# SCHE_Doan2.net
KiCad netlist of a schematic drawn in Altium Designer
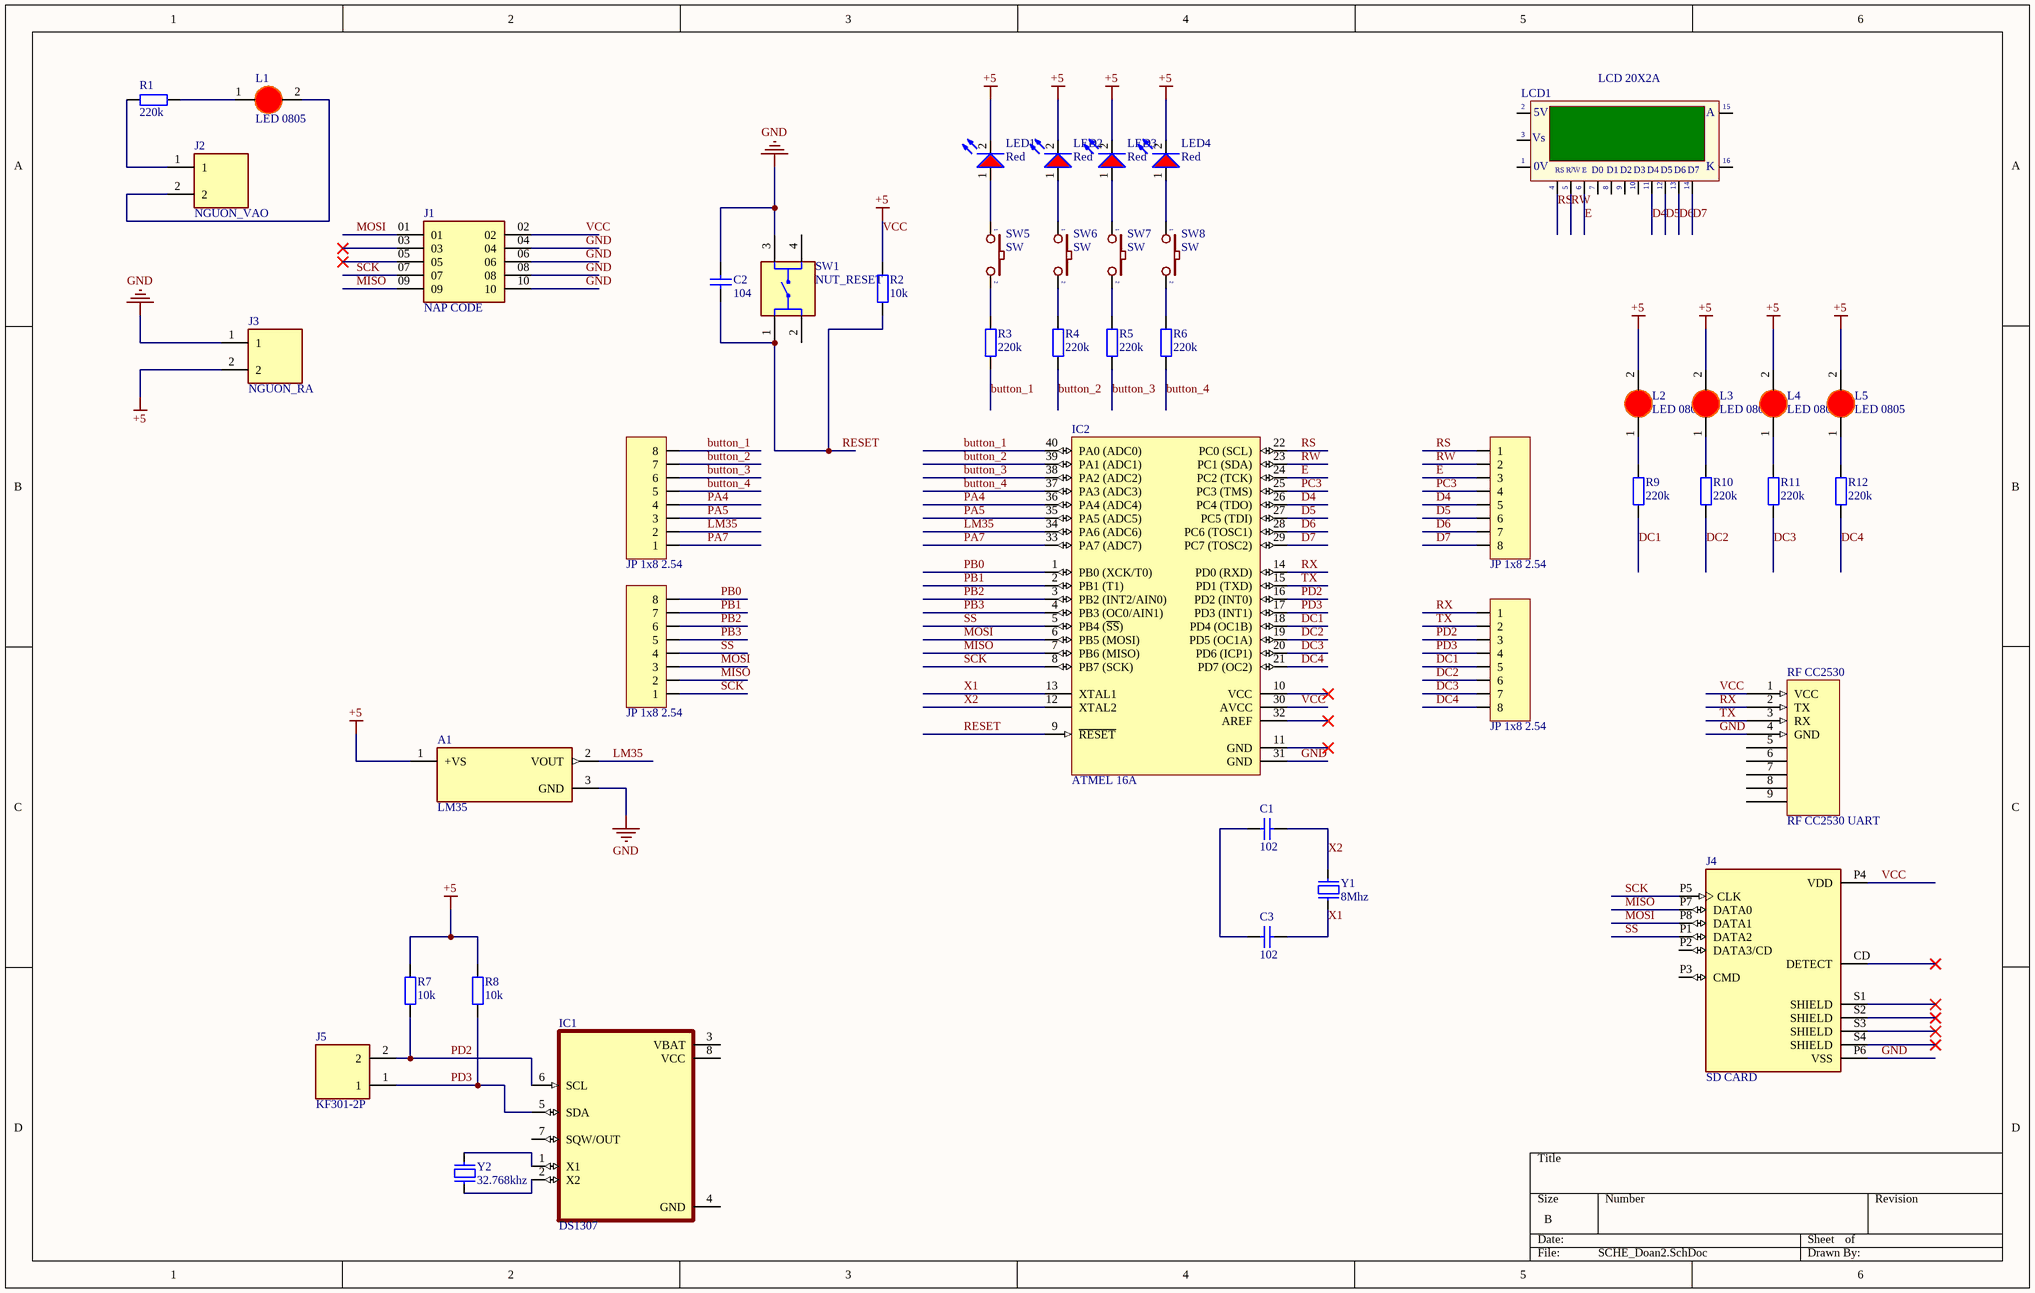
[diagram p0: SCHE_Doan2.SchDoc]

(export (version "E")
  (design (tool "Eeschema 10.0.6"))
  (components
    (comp (ref "A1")
      (value "LM35")
      (footprint "TO92127P521H735-3")
      (fields (field (name "MP") "LM35DZ/NOPB"))
      (libsource (lib "LM35DZ_NOPB") (part "LM35DZ/NOPB"))
    )
    (comp (ref "C1")
      (value "102")
      (footprint "tu gom")
      (description "Cắm")
      (libsource (lib "Altium_Lib_by_KhueNguyenCreator") (part "Tu gom 102 50V"))
    )
    (comp (ref "C2")
      (value "104")
      (footprint "tu gom")
      (description "Cắm")
      (libsource (lib "Altium_Lib_by_KhueNguyenCreator") (part "Tu gom 104 50V"))
    )
    (comp (ref "C3")
      (value "102")
      (footprint "tu gom")
      (description "Cắm")
      (libsource (lib "Altium_Lib_by_KhueNguyenCreator") (part "Tu gom 102 50V"))
    )
    (comp (ref "IC1")
      (value "DS1307")
      (footprint "DIP794W47P254L991H457Q8")
      (description "Real Time Clock _RTC_ IC Clock/Calendar 56B IÂ²C, 2-Wire Serial 8-DIP _0.300, 7.62mm_")
      (fields (field (name "MF") "Maxim Integrated"))
      (libsource (lib "DS1307") (part "DS1307"))
    )
    (comp (ref "IC2")
      (value "ATMEL 16A")
      (footprint "DIP40/W0.6")
      (description "8-Bit AVR Microcontroller with 16K Bytes of In-System Programmable Flash Memory")
      (libsource (lib "TechMT.VN_Lib_Project v2") (part "ATmega16A-PU"))
    )
    (comp (ref "J1")
      (value "NAP CODE")
      (footprint "SAMTEC_ZSS-105-09-L-D-1290")
      (fields (field (name "MP") "ZSS-105-09-L-D-1290"))
      (libsource (lib "ZSS-105-09-L-D-1290") (part "ZSS-105-09-L-D-1290"))
    )
    (comp (ref "J2")
      (value "NGUON_VAO")
      (footprint "HANDSON_KF301-2P")
      (description "2 Pin Terminal Block 5mm Pitch")
      (fields (field (name "MF") "Handson Technology") (field (name "MP") "KF301-2P"))
      (libsource (lib "") (part "KF301-2P_1"))
    )
    (comp (ref "J3")
      (value "NGUON_RA")
      (footprint "HANDSON_KF301-2P")
      (description "2 Pin Terminal Block 5mm Pitch")
      (fields (field (name "MF") "Handson Technology") (field (name "MP") "KF301-2P"))
      (libsource (lib "") (part "KF301-2P_1"))
    )
    (comp (ref "J4")
      (value "SD CARD")
      (footprint "GCT_MEM2051-00-195-00-A_REVD1")
      (fields (field (name "MP") "MEM2051-00-195-00-A_REVD1"))
      (libsource (lib "MEM2051-00-195-00-A_REVD1") (part "MEM2051-00-195-00-A_REVD1"))
    )
    (comp (ref "J5")
      (value "KF301-2P")
      (footprint "HANDSON_KF301-2P")
      (description "2 Pin Terminal Block 5mm Pitch")
      (fields (field (name "MF") "Handson Technology"))
      (libsource (lib "KF301-2P") (part "KF301-2P"))
    )
    (comp (ref "JP1")
      (value "JP 1x8 2.54")
      (footprint "JP 1x8 CT")
      (description "Cắm")
      (libsource (lib "") (part "JP 1x8 2.54 Cai Thang_1"))
    )
    (comp (ref "JP2")
      (value "JP 1x8 2.54")
      (footprint "JP 1x8 CT")
      (description "Cắm")
      (libsource (lib "Altium_Lib_by_KhueNguyenCreator") (part "JP 1x8 2.54 Cai Thang"))
    )
    (comp (ref "JP3")
      (value "JP 1x8 2.54")
      (footprint "JP 1x8 CT")
      (description "Cắm")
      (libsource (lib "Altium_Lib_by_KhueNguyenCreator") (part "JP 1x8 2.54 Cai Thang"))
    )
    (comp (ref "JP4")
      (value "JP 1x8 2.54")
      (footprint "JP 1x8 CT")
      (description "Cắm")
      (libsource (lib "") (part "JP 1x8 2.54 Cai Thang_1"))
    )
    (comp (ref "L1")
      (value "LED 0805")
      (footprint "LED-0805-Red")
      (description "Dán")
      (libsource (lib "Altium_Lib_by_KhueNguyenCreator") (part "LED 0805 Do"))
    )
    (comp (ref "L2")
      (value "LED 0805")
      (footprint "LED-0805-Red")
      (description "Dán")
      (libsource (lib "Altium_Lib_by_KhueNguyenCreator") (part "LED 0805 Do"))
    )
    (comp (ref "L3")
      (value "LED 0805")
      (footprint "LED-0805-Red")
      (description "Dán")
      (libsource (lib "Altium_Lib_by_KhueNguyenCreator") (part "LED 0805 Do"))
    )
    (comp (ref "L4")
      (value "LED 0805")
      (footprint "LED-0805-Red")
      (description "Dán")
      (libsource (lib "Altium_Lib_by_KhueNguyenCreator") (part "LED 0805 Do"))
    )
    (comp (ref "L5")
      (value "LED 0805")
      (footprint "LED-0805-Red")
      (description "Dán")
      (libsource (lib "Altium_Lib_by_KhueNguyenCreator") (part "LED 0805 Do"))
    )
    (comp (ref "LCD1")
      (value "LCD 20X2A")
      (footprint "LCD16X2")
      (description "LCD dipslay 16 char, 2 line")
      (libsource (lib "TechMT.VN_Lib_Project v1.0") (part "LCD16x2A"))
    )
    (comp (ref "LED1")
      (value "Red")
      (footprint "LED-RED-0805")
      (description "LED Red 2mA 1.8V 0805")
      (fields (field (name "Comment") "LED-Red"))
      (libsource (lib "TechMT.VN_Lib_Project v2") (part "Led-Red"))
    )
    (comp (ref "LED2")
      (value "Red")
      (footprint "LED-RED-0805")
      (description "LED Red 2mA 1.8V 0805")
      (fields (field (name "Comment") "LED-Red"))
      (libsource (lib "TechMT.VN_Lib_Project v2") (part "Led-Red"))
    )
    (comp (ref "LED3")
      (value "Red")
      (footprint "LED-RED-0805")
      (description "LED Red 2mA 1.8V 0805")
      (fields (field (name "Comment") "LED-Red"))
      (libsource (lib "TechMT.VN_Lib_Project v2") (part "Led-Red"))
    )
    (comp (ref "LED4")
      (value "Red")
      (footprint "LED-RED-0805")
      (description "LED Red 2mA 1.8V 0805")
      (fields (field (name "Comment") "LED-Red"))
      (libsource (lib "TechMT.VN_Lib_Project v2") (part "Led-Red"))
    )
    (comp (ref "R1")
      (value "220k")
      (footprint "tro smd 0805")
      (description "Dán")
      (libsource (lib "Altium_Lib_by_KhueNguyenCreator") (part "Tro 0805 1% 220k"))
    )
    (comp (ref "R2")
      (value "10k")
      (footprint "tro smd 0805")
      (description "Dán")
      (libsource (lib "Altium_Lib_by_KhueNguyenCreator") (part "Tro 0805 1% 10k"))
    )
    (comp (ref "R3")
      (value "220k")
      (footprint "tro smd 0805")
      (description "Dán")
      (libsource (lib "Altium_Lib_by_KhueNguyenCreator") (part "Tro 0805 1% 220k"))
    )
    (comp (ref "R4")
      (value "220k")
      (footprint "tro smd 0805")
      (description "Dán")
      (libsource (lib "Altium_Lib_by_KhueNguyenCreator") (part "Tro 0805 1% 220k"))
    )
    (comp (ref "R5")
      (value "220k")
      (footprint "tro smd 0805")
      (description "Dán")
      (libsource (lib "Altium_Lib_by_KhueNguyenCreator") (part "Tro 0805 1% 220k"))
    )
    (comp (ref "R6")
      (value "220k")
      (footprint "tro smd 0805")
      (description "Dán")
      (libsource (lib "Altium_Lib_by_KhueNguyenCreator") (part "Tro 0805 1% 220k"))
    )
    (comp (ref "R7")
      (value "10k")
      (footprint "tro smd 0805")
      (description "Dán")
      (libsource (lib "Altium_Lib_by_KhueNguyenCreator") (part "Tro 0805 1% 10k"))
    )
    (comp (ref "R8")
      (value "10k")
      (footprint "tro smd 0805")
      (description "Dán")
      (libsource (lib "Altium_Lib_by_KhueNguyenCreator") (part "Tro 0805 1% 10k"))
    )
    (comp (ref "R9")
      (value "220k")
      (footprint "tro smd 0805")
      (description "Dán")
      (libsource (lib "Altium_Lib_by_KhueNguyenCreator") (part "Tro 0805 1% 220k"))
    )
    (comp (ref "R10")
      (value "220k")
      (footprint "tro smd 0805")
      (description "Dán")
      (libsource (lib "Altium_Lib_by_KhueNguyenCreator") (part "Tro 0805 1% 220k"))
    )
    (comp (ref "R11")
      (value "220k")
      (footprint "tro smd 0805")
      (description "Dán")
      (libsource (lib "Altium_Lib_by_KhueNguyenCreator") (part "Tro 0805 1% 220k"))
    )
    (comp (ref "R12")
      (value "220k")
      (footprint "tro smd 0805")
      (description "Dán")
      (libsource (lib "Altium_Lib_by_KhueNguyenCreator") (part "Tro 0805 1% 220k"))
    )
    (comp (ref "RF CC2530")
      (value "RF CC2530 UART")
      (footprint "CC2530")
      (description "IC chính: CC2530, 15.5 x 31.5mm")
      (libsource (lib "TechMT.VN_Lib_Project v2") (part "RF CC2530 UART 2.4G"))
    )
    (comp (ref "SW1")
      (value "NUT_RESET")
      (footprint "SW_1825910-6-4")
      (description "Switch Tactile OFF (ON) SPST Round Button PC Pins 0.05A 24VDC 100000Cycles 1.57N Thru-Hole Loose")
      (fields (field (name "MP") "1825910-6"))
      (libsource (lib "1825910-6") (part "1825910-6"))
    )
    (comp (ref "SW5")
      (value "SW")
      (footprint "SW1-SMD")
      (description "Switch button 2 pin")
      (libsource (lib "TechMT.VN_Lib_Project v2") (part "SW2"))
    )
    (comp (ref "SW6")
      (value "SW")
      (footprint "SW1-SMD")
      (description "Switch button 2 pin")
      (libsource (lib "TechMT.VN_Lib_Project v2") (part "SW2"))
    )
    (comp (ref "SW7")
      (value "SW")
      (footprint "SW1-SMD")
      (description "Switch button 2 pin")
      (libsource (lib "TechMT.VN_Lib_Project v2") (part "SW2"))
    )
    (comp (ref "SW8")
      (value "SW")
      (footprint "SW1-SMD")
      (description "Switch button 2 pin")
      (libsource (lib "TechMT.VN_Lib_Project v2") (part "SW2"))
    )
    (comp (ref "Y1")
      (value "8Mhz")
      (footprint "Thach Anh 2 Chan 32,768 KHz")
      (description "Crystal For all Crystal 2pin.")
      (libsource (lib "Altium_Lib_by_KhueNguyenCreator") (part "Thach Anh 2 chan 32,768 Khz"))
    )
    (comp (ref "Y2")
      (value "32.768khz")
      (footprint "Thach Anh 2 Chan 32,768 KHz")
      (description "Crystal For all Crystal 2pin.")
      (libsource (lib "Altium_Lib_by_KhueNguyenCreator") (part "Thach Anh 2 chan 32,768 Khz"))
    )
  )
  (nets
    (net (code "1") (name "+5") (class "Default")
      (node (ref "A1") (pin "1") (pinfunction "+VS_1") (pintype "power_in"))
      (node (ref "IC2") (pin "30") (pinfunction "AVCC_30") (pintype "power_in"))
      (node (ref "J1") (pin "02") (pinfunction "02_02") (pintype "passive"))
      (node (ref "J3") (pin "2") (pinfunction "2_2") (pintype "passive"))
      (node (ref "J4") (pin "P4") (pinfunction "VDD_P4") (pintype "power_in"))
      (node (ref "L2") (pin "2") (pinfunction "K_2") (pintype "passive"))
      (node (ref "L3") (pin "2") (pinfunction "K_2") (pintype "passive"))
      (node (ref "L4") (pin "2") (pinfunction "K_2") (pintype "passive"))
      (node (ref "L5") (pin "2") (pinfunction "K_2") (pintype "passive"))
      (node (ref "LED1") (pin "2") (pinfunction "K_2") (pintype "passive"))
      (node (ref "LED2") (pin "2") (pinfunction "K_2") (pintype "passive"))
      (node (ref "LED3") (pin "2") (pinfunction "K_2") (pintype "passive"))
      (node (ref "LED4") (pin "2") (pinfunction "K_2") (pintype "passive"))
      (node (ref "R2") (pin "2") (pinfunction "2_2") (pintype "passive"))
      (node (ref "R7") (pin "2") (pinfunction "2_2") (pintype "passive"))
      (node (ref "R8") (pin "2") (pinfunction "2_2") (pintype "passive"))
      (node (ref "RF CC2530") (pin "1") (pinfunction "VCC_1") (pintype "input"))
    )
    (net (code "2") (name "/D4") (class "Default")
      (node (ref "IC2") (pin "26") (pinfunction "PC4_(TDO)_26") (pintype "bidirectional"))
      (node (ref "JP1") (pin "5") (pinfunction "5_5") (pintype "passive"))
      (node (ref "LCD1") (pin "11") (pinfunction "D4_11") (pintype "passive"))
    )
    (net (code "3") (name "/D5") (class "Default")
      (node (ref "IC2") (pin "27") (pinfunction "PC5_(TDI)_27") (pintype "bidirectional"))
      (node (ref "JP1") (pin "6") (pinfunction "6_6") (pintype "passive"))
      (node (ref "LCD1") (pin "12") (pinfunction "D5_12") (pintype "passive"))
    )
    (net (code "4") (name "/D6") (class "Default")
      (node (ref "IC2") (pin "28") (pinfunction "PC6_(TOSC1)_28") (pintype "bidirectional"))
      (node (ref "JP1") (pin "7") (pinfunction "7_7") (pintype "passive"))
      (node (ref "LCD1") (pin "13") (pinfunction "D6_13") (pintype "passive"))
    )
    (net (code "5") (name "/D7") (class "Default")
      (node (ref "IC2") (pin "29") (pinfunction "PC7_(TOSC2)_29") (pintype "bidirectional"))
      (node (ref "JP1") (pin "8") (pinfunction "8_8") (pintype "passive"))
      (node (ref "LCD1") (pin "14") (pinfunction "D7_14") (pintype "passive"))
    )
    (net (code "6") (name "/DC1") (class "Default")
      (node (ref "IC2") (pin "18") (pinfunction "PD4_(OC1B)_18") (pintype "bidirectional"))
      (node (ref "JP4") (pin "5") (pinfunction "5_5") (pintype "passive"))
      (node (ref "R9") (pin "1") (pinfunction "1_1") (pintype "passive"))
    )
    (net (code "7") (name "/DC2") (class "Default")
      (node (ref "IC2") (pin "19") (pinfunction "PD5_(OC1A)_19") (pintype "bidirectional"))
      (node (ref "JP4") (pin "6") (pinfunction "6_6") (pintype "passive"))
      (node (ref "R10") (pin "1") (pinfunction "1_1") (pintype "passive"))
    )
    (net (code "8") (name "/DC3") (class "Default")
      (node (ref "IC2") (pin "20") (pinfunction "PD6_(ICP1)_20") (pintype "bidirectional"))
      (node (ref "JP4") (pin "7") (pinfunction "7_7") (pintype "passive"))
      (node (ref "R11") (pin "1") (pinfunction "1_1") (pintype "passive"))
    )
    (net (code "9") (name "/DC4") (class "Default")
      (node (ref "IC2") (pin "21") (pinfunction "PD7_(OC2)_21") (pintype "bidirectional"))
      (node (ref "JP4") (pin "8") (pinfunction "8_8") (pintype "passive"))
      (node (ref "R12") (pin "1") (pinfunction "1_1") (pintype "passive"))
    )
    (net (code "10") (name "/E") (class "Default")
      (node (ref "IC2") (pin "24") (pinfunction "PC2_(TCK)_24") (pintype "bidirectional"))
      (node (ref "JP1") (pin "3") (pinfunction "3_3") (pintype "passive"))
      (node (ref "LCD1") (pin "6") (pinfunction "~{EN}_6") (pintype "passive"))
    )
    (net (code "11") (name "/LM35") (class "Default")
      (node (ref "A1") (pin "2") (pinfunction "VOUT_2") (pintype "output"))
      (node (ref "IC2") (pin "34") (pinfunction "PA6_(ADC6)_34") (pintype "bidirectional"))
      (node (ref "JP2") (pin "2") (pinfunction "2_2") (pintype "passive"))
    )
    (net (code "12") (name "/MISO") (class "Default")
      (node (ref "IC2") (pin "7") (pinfunction "PB6_(MISO)_7") (pintype "bidirectional"))
      (node (ref "J1") (pin "09") (pinfunction "09_09") (pintype "passive"))
      (node (ref "J4") (pin "P7") (pinfunction "DATA0_P7") (pintype "bidirectional"))
      (node (ref "JP3") (pin "2") (pinfunction "2_2") (pintype "passive"))
    )
    (net (code "13") (name "/MOSI") (class "Default")
      (node (ref "IC2") (pin "6") (pinfunction "PB5_(MOSI)_6") (pintype "bidirectional"))
      (node (ref "J1") (pin "01") (pinfunction "01_01") (pintype "passive"))
      (node (ref "J4") (pin "P8") (pinfunction "DATA1_P8") (pintype "bidirectional"))
      (node (ref "JP3") (pin "3") (pinfunction "3_3") (pintype "passive"))
    )
    (net (code "14") (name "/PA4") (class "Default")
      (node (ref "IC2") (pin "36") (pinfunction "PA4_(ADC4)_36") (pintype "bidirectional"))
      (node (ref "JP2") (pin "4") (pinfunction "4_4") (pintype "passive"))
    )
    (net (code "15") (name "/PA5") (class "Default")
      (node (ref "IC2") (pin "35") (pinfunction "PA5_(ADC5)_35") (pintype "bidirectional"))
      (node (ref "JP2") (pin "3") (pinfunction "3_3") (pintype "passive"))
    )
    (net (code "16") (name "/PA7") (class "Default")
      (node (ref "IC2") (pin "33") (pinfunction "PA7_(ADC7)_33") (pintype "bidirectional"))
      (node (ref "JP2") (pin "1") (pinfunction "1_1") (pintype "passive"))
    )
    (net (code "17") (name "/PB0") (class "Default")
      (node (ref "IC2") (pin "1") (pinfunction "PB0_(XCK/T0)_1") (pintype "bidirectional"))
      (node (ref "JP3") (pin "8") (pinfunction "8_8") (pintype "passive"))
    )
    (net (code "18") (name "/PB1") (class "Default")
      (node (ref "IC2") (pin "2") (pinfunction "PB1_(T1)_2") (pintype "bidirectional"))
      (node (ref "JP3") (pin "7") (pinfunction "7_7") (pintype "passive"))
    )
    (net (code "19") (name "/PB2") (class "Default")
      (node (ref "IC2") (pin "3") (pinfunction "PB2_(INT2/AIN0)_3") (pintype "bidirectional"))
      (node (ref "JP3") (pin "6") (pinfunction "6_6") (pintype "passive"))
    )
    (net (code "20") (name "/PB3") (class "Default")
      (node (ref "IC2") (pin "4") (pinfunction "PB3_(OC0/AIN1)_4") (pintype "bidirectional"))
      (node (ref "JP3") (pin "5") (pinfunction "5_5") (pintype "passive"))
    )
    (net (code "21") (name "/PC3") (class "Default")
      (node (ref "IC2") (pin "25") (pinfunction "PC3_(TMS)_25") (pintype "bidirectional"))
      (node (ref "JP1") (pin "4") (pinfunction "4_4") (pintype "passive"))
    )
    (net (code "22") (name "/PD2") (class "Default")
      (node (ref "IC1") (pin "6") (pinfunction "SCL_6") (pintype "input"))
      (node (ref "IC2") (pin "16") (pinfunction "PD2_(INT0)_16") (pintype "bidirectional"))
      (node (ref "J5") (pin "2") (pinfunction "2_2") (pintype "passive"))
      (node (ref "JP4") (pin "3") (pinfunction "3_3") (pintype "passive"))
      (node (ref "R7") (pin "1") (pinfunction "1_1") (pintype "passive"))
    )
    (net (code "23") (name "/PD3") (class "Default")
      (node (ref "IC1") (pin "5") (pinfunction "SDA_5") (pintype "bidirectional"))
      (node (ref "IC2") (pin "17") (pinfunction "PD3_(INT1)_17") (pintype "bidirectional"))
      (node (ref "J5") (pin "1") (pinfunction "1_1") (pintype "passive"))
      (node (ref "JP4") (pin "4") (pinfunction "4_4") (pintype "passive"))
      (node (ref "R8") (pin "1") (pinfunction "1_1") (pintype "passive"))
    )
    (net (code "24") (name "/RESET") (class "Default")
      (node (ref "C2") (pin "2") (pinfunction "2_2") (pintype "passive"))
      (node (ref "IC2") (pin "9") (pinfunction "~{RESET}_9") (pintype "input"))
      (node (ref "R2") (pin "1") (pinfunction "1_1") (pintype "passive"))
      (node (ref "SW1") (pin "1") (pinfunction "1_1") (pintype "passive"))
    )
    (net (code "25") (name "/RS") (class "Default")
      (node (ref "IC2") (pin "22") (pinfunction "PC0_(SCL)_22") (pintype "bidirectional"))
      (node (ref "JP1") (pin "1") (pinfunction "1_1") (pintype "passive"))
      (node (ref "LCD1") (pin "4") (pinfunction "RS_4") (pintype "passive"))
    )
    (net (code "26") (name "/RW") (class "Default")
      (node (ref "IC2") (pin "23") (pinfunction "PC1_(SDA)_23") (pintype "bidirectional"))
      (node (ref "JP1") (pin "2") (pinfunction "2_2") (pintype "passive"))
      (node (ref "LCD1") (pin "5") (pinfunction "R/~{W}_5") (pintype "passive"))
    )
    (net (code "27") (name "/RX") (class "Default")
      (node (ref "IC2") (pin "14") (pinfunction "PD0_(RXD)_14") (pintype "bidirectional"))
      (node (ref "JP4") (pin "1") (pinfunction "1_1") (pintype "passive"))
      (node (ref "RF CC2530") (pin "2") (pinfunction "TX_2") (pintype "input"))
    )
    (net (code "28") (name "/SCK") (class "Default")
      (node (ref "IC2") (pin "8") (pinfunction "PB7_(SCK)_8") (pintype "bidirectional"))
      (node (ref "J1") (pin "07") (pinfunction "07_07") (pintype "passive"))
      (node (ref "J4") (pin "P5") (pinfunction "CLK_P5") (pintype "input"))
      (node (ref "JP3") (pin "1") (pinfunction "1_1") (pintype "passive"))
    )
    (net (code "29") (name "/SS") (class "Default")
      (node (ref "IC2") (pin "5") (pinfunction "PB4_(~{SS})_5") (pintype "bidirectional"))
      (node (ref "J4") (pin "P1") (pinfunction "DATA2_P1") (pintype "bidirectional"))
      (node (ref "JP3") (pin "4") (pinfunction "4_4") (pintype "passive"))
    )
    (net (code "30") (name "/TX") (class "Default")
      (node (ref "IC2") (pin "15") (pinfunction "PD1_(TXD)_15") (pintype "bidirectional"))
      (node (ref "JP4") (pin "2") (pinfunction "2_2") (pintype "passive"))
      (node (ref "RF CC2530") (pin "3") (pinfunction "RX_3") (pintype "input"))
    )
    (net (code "31") (name "/X1") (class "Default")
      (node (ref "C3") (pin "1") (pinfunction "1_1") (pintype "passive"))
      (node (ref "IC2") (pin "13") (pinfunction "XTAL1_13") (pintype "passive"))
      (node (ref "Y1") (pin "1") (pinfunction "1_1") (pintype "passive"))
    )
    (net (code "32") (name "/X2") (class "Default")
      (node (ref "C1") (pin "1") (pinfunction "1_1") (pintype "passive"))
      (node (ref "IC2") (pin "12") (pinfunction "XTAL2_12") (pintype "passive"))
      (node (ref "Y1") (pin "2") (pinfunction "2_2") (pintype "passive"))
    )
    (net (code "33") (name "/button_1") (class "Default")
      (node (ref "IC2") (pin "40") (pinfunction "PA0_(ADC0)_40") (pintype "bidirectional"))
      (node (ref "JP2") (pin "8") (pinfunction "8_8") (pintype "passive"))
      (node (ref "R3") (pin "1") (pinfunction "1_1") (pintype "passive"))
    )
    (net (code "34") (name "/button_2") (class "Default")
      (node (ref "IC2") (pin "39") (pinfunction "PA1_(ADC1)_39") (pintype "bidirectional"))
      (node (ref "JP2") (pin "7") (pinfunction "7_7") (pintype "passive"))
      (node (ref "R4") (pin "1") (pinfunction "1_1") (pintype "passive"))
    )
    (net (code "35") (name "/button_3") (class "Default")
      (node (ref "IC2") (pin "38") (pinfunction "PA2_(ADC2)_38") (pintype "bidirectional"))
      (node (ref "JP2") (pin "6") (pinfunction "6_6") (pintype "passive"))
      (node (ref "R5") (pin "1") (pinfunction "1_1") (pintype "passive"))
    )
    (net (code "36") (name "/button_4") (class "Default")
      (node (ref "IC2") (pin "37") (pinfunction "PA3_(ADC3)_37") (pintype "bidirectional"))
      (node (ref "JP2") (pin "5") (pinfunction "5_5") (pintype "passive"))
      (node (ref "R6") (pin "1") (pinfunction "1_1") (pintype "passive"))
    )
    (net (code "37") (name "GND") (class "Default")
      (node (ref "A1") (pin "3") (pinfunction "GND_3") (pintype "power_in"))
      (node (ref "C2") (pin "1") (pinfunction "1_1") (pintype "passive"))
      (node (ref "IC2") (pin "31") (pinfunction "GND_31") (pintype "power_in"))
      (node (ref "J1") (pin "04") (pinfunction "04_04") (pintype "passive"))
      (node (ref "J1") (pin "06") (pinfunction "06_06") (pintype "passive"))
      (node (ref "J1") (pin "08") (pinfunction "08_08") (pintype "passive"))
      (node (ref "J1") (pin "10") (pinfunction "10_10") (pintype "passive"))
      (node (ref "J3") (pin "1") (pinfunction "1_1") (pintype "passive"))
      (node (ref "J4") (pin "P6") (pinfunction "VSS_P6") (pintype "power_in"))
      (node (ref "RF CC2530") (pin "4") (pinfunction "GND_4") (pintype "input"))
      (node (ref "SW1") (pin "3") (pinfunction "3_3") (pintype "passive"))
    )
    (net (code "38") (name "Net-(C1-Pad2)") (class "Default")
      (node (ref "C1") (pin "2") (pinfunction "2_2") (pintype "passive"))
      (node (ref "C3") (pin "2") (pinfunction "2_2") (pintype "passive"))
    )
    (net (code "39") (name "Net-(IC1-X1)") (class "Default")
      (node (ref "IC1") (pin "1") (pinfunction "X1_1") (pintype "bidirectional"))
      (node (ref "Y2") (pin "2") (pinfunction "2_2") (pintype "passive"))
    )
    (net (code "40") (name "Net-(IC1-X2)") (class "Default")
      (node (ref "IC1") (pin "2") (pinfunction "X2_2") (pintype "bidirectional"))
      (node (ref "Y2") (pin "1") (pinfunction "1_1") (pintype "passive"))
    )
    (net (code "41") (name "Net-(J2-Pad1)") (class "Default")
      (node (ref "J2") (pin "1") (pinfunction "1_1") (pintype "passive"))
      (node (ref "R1") (pin "1") (pinfunction "1_1") (pintype "passive"))
    )
    (net (code "42") (name "Net-(L1-A)") (class "Default")
      (node (ref "L1") (pin "1") (pinfunction "A_1") (pintype "passive"))
      (node (ref "R1") (pin "2") (pinfunction "2_2") (pintype "passive"))
    )
    (net (code "43") (name "Net-(L1-K)") (class "Default")
      (node (ref "J2") (pin "2") (pinfunction "2_2") (pintype "passive"))
      (node (ref "L1") (pin "2") (pinfunction "K_2") (pintype "passive"))
    )
    (net (code "44") (name "Net-(L2-A)") (class "Default")
      (node (ref "L2") (pin "1") (pinfunction "A_1") (pintype "passive"))
      (node (ref "R9") (pin "2") (pinfunction "2_2") (pintype "passive"))
    )
    (net (code "45") (name "Net-(L3-A)") (class "Default")
      (node (ref "L3") (pin "1") (pinfunction "A_1") (pintype "passive"))
      (node (ref "R10") (pin "2") (pinfunction "2_2") (pintype "passive"))
    )
    (net (code "46") (name "Net-(L4-A)") (class "Default")
      (node (ref "L4") (pin "1") (pinfunction "A_1") (pintype "passive"))
      (node (ref "R11") (pin "2") (pinfunction "2_2") (pintype "passive"))
    )
    (net (code "47") (name "Net-(L5-A)") (class "Default")
      (node (ref "L5") (pin "1") (pinfunction "A_1") (pintype "passive"))
      (node (ref "R12") (pin "2") (pinfunction "2_2") (pintype "passive"))
    )
    (net (code "48") (name "Net-(LED1-A)") (class "Default")
      (node (ref "LED1") (pin "1") (pinfunction "A_1") (pintype "passive"))
      (node (ref "SW5") (pin "1") (pinfunction "1_1") (pintype "passive"))
    )
    (net (code "49") (name "Net-(LED2-A)") (class "Default")
      (node (ref "LED2") (pin "1") (pinfunction "A_1") (pintype "passive"))
      (node (ref "SW6") (pin "1") (pinfunction "1_1") (pintype "passive"))
    )
    (net (code "50") (name "Net-(LED3-A)") (class "Default")
      (node (ref "LED3") (pin "1") (pinfunction "A_1") (pintype "passive"))
      (node (ref "SW7") (pin "1") (pinfunction "1_1") (pintype "passive"))
    )
    (net (code "51") (name "Net-(LED4-A)") (class "Default")
      (node (ref "LED4") (pin "1") (pinfunction "A_1") (pintype "passive"))
      (node (ref "SW8") (pin "1") (pinfunction "1_1") (pintype "passive"))
    )
    (net (code "52") (name "Net-(R3-Pad2)") (class "Default")
      (node (ref "R3") (pin "2") (pinfunction "2_2") (pintype "passive"))
      (node (ref "SW5") (pin "2") (pinfunction "2_2") (pintype "passive"))
    )
    (net (code "53") (name "Net-(R4-Pad2)") (class "Default")
      (node (ref "R4") (pin "2") (pinfunction "2_2") (pintype "passive"))
      (node (ref "SW6") (pin "2") (pinfunction "2_2") (pintype "passive"))
    )
    (net (code "54") (name "Net-(R5-Pad2)") (class "Default")
      (node (ref "R5") (pin "2") (pinfunction "2_2") (pintype "passive"))
      (node (ref "SW7") (pin "2") (pinfunction "2_2") (pintype "passive"))
    )
    (net (code "55") (name "Net-(R6-Pad2)") (class "Default")
      (node (ref "R6") (pin "2") (pinfunction "2_2") (pintype "passive"))
      (node (ref "SW8") (pin "2") (pinfunction "2_2") (pintype "passive"))
    )
    (net (code "56") (name "unconnected-(IC1-GND-Pad4)") (class "Default")
      (node (ref "IC1") (pin "4") (pinfunction "GND_4") (pintype "power_in"))
    )
    (net (code "57") (name "unconnected-(IC1-SQW{slash}OUT-Pad7)") (class "Default")
      (node (ref "IC1") (pin "7") (pinfunction "SQW/OUT_7") (pintype "bidirectional"))
    )
    (net (code "58") (name "unconnected-(IC1-VBAT-Pad3)") (class "Default")
      (node (ref "IC1") (pin "3") (pinfunction "VBAT_3") (pintype "power_in"))
    )
    (net (code "59") (name "unconnected-(IC1-VCC-Pad8)") (class "Default")
      (node (ref "IC1") (pin "8") (pinfunction "VCC_8") (pintype "power_in"))
    )
    (net (code "60") (name "unconnected-(IC2-AREF-Pad32)") (class "Default")
      (node (ref "IC2") (pin "32") (pinfunction "AREF_32") (pintype "power_in+no_connect"))
    )
    (net (code "61") (name "unconnected-(IC2-GND-Pad11)") (class "Default")
      (node (ref "IC2") (pin "11") (pinfunction "GND_11") (pintype "power_in+no_connect"))
    )
    (net (code "62") (name "unconnected-(IC2-VCC-Pad10)") (class "Default")
      (node (ref "IC2") (pin "10") (pinfunction "VCC_10") (pintype "power_in+no_connect"))
    )
    (net (code "63") (name "unconnected-(J1-Pad03)") (class "Default")
      (node (ref "J1") (pin "03") (pinfunction "03_03") (pintype "passive+no_connect"))
    )
    (net (code "64") (name "unconnected-(J1-Pad05)") (class "Default")
      (node (ref "J1") (pin "05") (pinfunction "05_05") (pintype "passive+no_connect"))
    )
    (net (code "65") (name "unconnected-(J4-CMD-PadP3)") (class "Default")
      (node (ref "J4") (pin "P3") (pinfunction "CMD_P3") (pintype "bidirectional"))
    )
    (net (code "66") (name "unconnected-(J4-DATA3{slash}CD-PadP2)") (class "Default")
      (node (ref "J4") (pin "P2") (pinfunction "DATA3/CD_P2") (pintype "bidirectional"))
    )
    (net (code "67") (name "unconnected-(J4-DETECT-PadCD)") (class "Default")
      (node (ref "J4") (pin "CD") (pinfunction "DETECT_CD") (pintype "passive+no_connect"))
    )
    (net (code "68") (name "unconnected-(J4-SHIELD-PadS1)") (class "Default")
      (node (ref "J4") (pin "S1") (pinfunction "SHIELD_S1") (pintype "passive+no_connect"))
    )
    (net (code "69") (name "unconnected-(J4-SHIELD-PadS2)") (class "Default")
      (node (ref "J4") (pin "S2") (pinfunction "SHIELD_S2") (pintype "passive+no_connect"))
    )
    (net (code "70") (name "unconnected-(J4-SHIELD-PadS3)") (class "Default")
      (node (ref "J4") (pin "S3") (pinfunction "SHIELD_S3") (pintype "passive+no_connect"))
    )
    (net (code "71") (name "unconnected-(J4-SHIELD-PadS4)") (class "Default")
      (node (ref "J4") (pin "S4") (pinfunction "SHIELD_S4") (pintype "passive+no_connect"))
    )
    (net (code "72") (name "unconnected-(LCD1-A-Pad15)") (class "Default")
      (node (ref "LCD1") (pin "15") (pinfunction "A_15") (pintype "passive"))
    )
    (net (code "73") (name "unconnected-(LCD1-D0-Pad7)") (class "Default")
      (node (ref "LCD1") (pin "7") (pinfunction "D0_7") (pintype "passive"))
    )
    (net (code "74") (name "unconnected-(LCD1-D1-Pad8)") (class "Default")
      (node (ref "LCD1") (pin "8") (pinfunction "D1_8") (pintype "passive"))
    )
    (net (code "75") (name "unconnected-(LCD1-D2-Pad9)") (class "Default")
      (node (ref "LCD1") (pin "9") (pinfunction "D2_9") (pintype "passive"))
    )
    (net (code "76") (name "unconnected-(LCD1-D3-Pad10)") (class "Default")
      (node (ref "LCD1") (pin "10") (pinfunction "D3_10") (pintype "passive"))
    )
    (net (code "77") (name "unconnected-(LCD1-GND-Pad1)") (class "Default")
      (node (ref "LCD1") (pin "1") (pinfunction "GND_1") (pintype "passive"))
    )
    (net (code "78") (name "unconnected-(LCD1-K-Pad16)") (class "Default")
      (node (ref "LCD1") (pin "16") (pinfunction "K_16") (pintype "passive"))
    )
    (net (code "79") (name "unconnected-(LCD1-VDD-Pad2)") (class "Default")
      (node (ref "LCD1") (pin "2") (pinfunction "VDD_2") (pintype "passive"))
    )
    (net (code "80") (name "unconnected-(LCD1-VEE-Pad3)") (class "Default")
      (node (ref "LCD1") (pin "3") (pinfunction "VEE_3") (pintype "passive"))
    )
    (net (code "81") (name "unconnected-(RF CC2530-Pad5)") (class "Default")
      (node (ref "RF CC2530") (pin "5") (pintype "passive"))
    )
    (net (code "82") (name "unconnected-(RF CC2530-Pad6)") (class "Default")
      (node (ref "RF CC2530") (pin "6") (pintype "passive"))
    )
    (net (code "83") (name "unconnected-(RF CC2530-Pad7)") (class "Default")
      (node (ref "RF CC2530") (pin "7") (pintype "passive"))
    )
    (net (code "84") (name "unconnected-(RF CC2530-Pad8)") (class "Default")
      (node (ref "RF CC2530") (pin "8") (pintype "passive"))
    )
    (net (code "85") (name "unconnected-(RF CC2530-Pad9)") (class "Default")
      (node (ref "RF CC2530") (pin "9") (pintype "passive"))
    )
    (net (code "86") (name "unconnected-(SW1-Pad2)") (class "Default")
      (node (ref "SW1") (pin "2") (pinfunction "2_2") (pintype "passive"))
    )
    (net (code "87") (name "unconnected-(SW1-Pad4)") (class "Default")
      (node (ref "SW1") (pin "4") (pinfunction "4_4") (pintype "passive"))
    )
  )
)
